# esp32_cam_rev_B.net
KiCad netlist of a schematic drawn in EAGLE
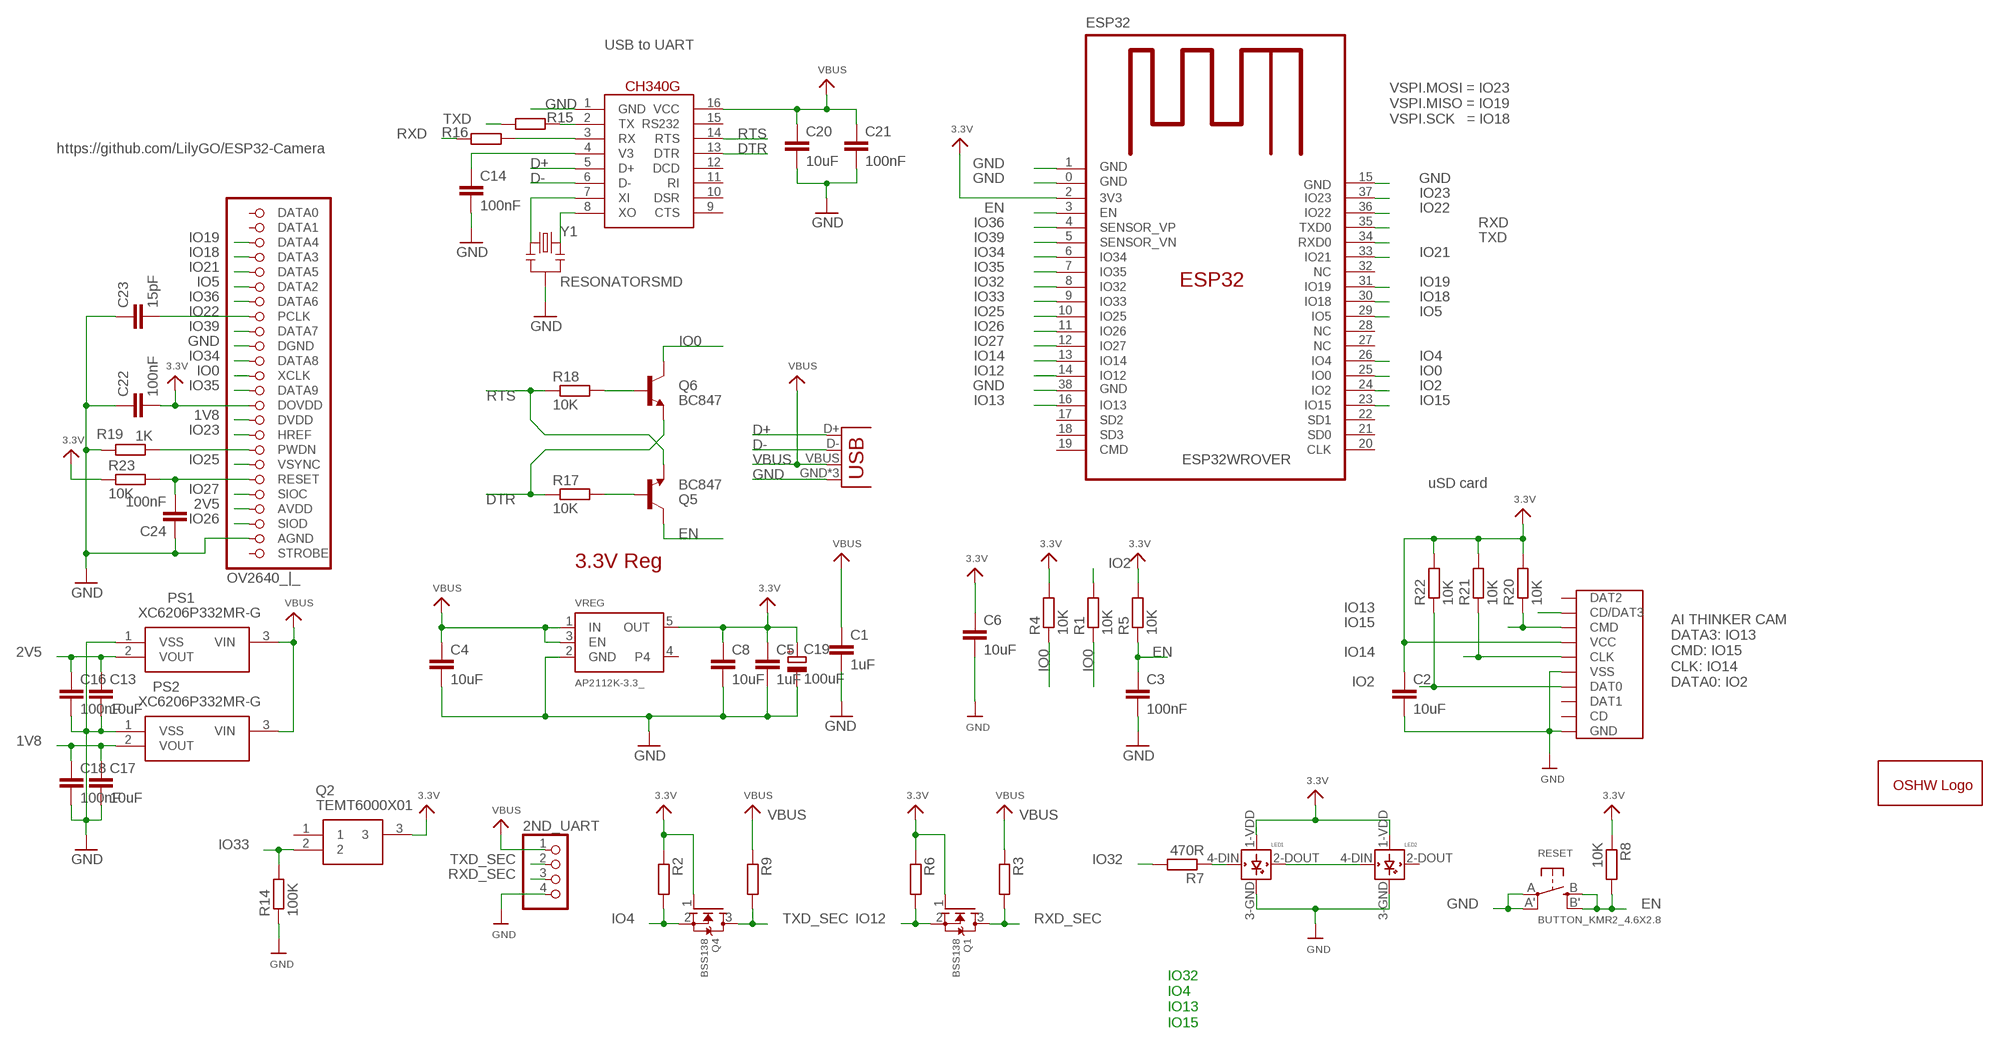
[diagram p0: schematic, sheet 1]

(export (version "E")
  (design (tool "Eeschema 10.0.6"))
  (components
    (comp (ref "2ND_UART")
      (value "JST_PH4")
      (footprint "eagle-import:JSTPH4")
      (libsource (lib "eagle-import") (part "JST_PH4"))
    )
    (comp (ref "C1")
      (value "1uF")
      (footprint "eagle-import:C0805K")
      (libsource (lib "eagle-import") (part "C-EUC0805K"))
    )
    (comp (ref "C2")
      (value "10uF")
      (footprint "eagle-import:C0805")
      (libsource (lib "eagle-import") (part "C-EUC0805"))
    )
    (comp (ref "C3")
      (value "100nF")
      (footprint "eagle-import:C0805K")
      (libsource (lib "eagle-import") (part "C-EUC0805K"))
    )
    (comp (ref "C4")
      (value "10uF")
      (footprint "eagle-import:C0805")
      (libsource (lib "eagle-import") (part "C-EUC0805"))
    )
    (comp (ref "C5")
      (value "1uF")
      (footprint "eagle-import:C0805")
      (libsource (lib "eagle-import") (part "C-EUC0805"))
    )
    (comp (ref "C6")
      (value "10uF")
      (footprint "eagle-import:C0805K")
      (libsource (lib "eagle-import") (part "C-EUC0805K"))
    )
    (comp (ref "C8")
      (value "10uF")
      (footprint "eagle-import:C0805")
      (libsource (lib "eagle-import") (part "C-EUC0805"))
    )
    (comp (ref "C13")
      (value "10uF")
      (footprint "eagle-import:C0805")
      (libsource (lib "eagle-import") (part "C-EUC0805"))
    )
    (comp (ref "C14")
      (value "100nF")
      (footprint "eagle-import:C0805K")
      (libsource (lib "eagle-import") (part "C-EUC0805K"))
    )
    (comp (ref "C16")
      (value "100nF")
      (footprint "eagle-import:C0805")
      (libsource (lib "eagle-import") (part "C-EUC0805"))
    )
    (comp (ref "C17")
      (value "10uF")
      (footprint "eagle-import:C0805")
      (libsource (lib "eagle-import") (part "C-EUC0805"))
    )
    (comp (ref "C18")
      (value "100nF")
      (footprint "eagle-import:C0805")
      (libsource (lib "eagle-import") (part "C-EUC0805"))
    )
    (comp (ref "C19")
      (value "100uF")
      (footprint "eagle-import:CT6032")
      (libsource (lib "eagle-import") (part "CPOL-EUCT6032"))
    )
    (comp (ref "C20")
      (value "10uF")
      (footprint "eagle-import:C0805")
      (libsource (lib "eagle-import") (part "C-EUC0805"))
    )
    (comp (ref "C21")
      (value "100nF")
      (footprint "eagle-import:C0805")
      (libsource (lib "eagle-import") (part "C-EUC0805"))
    )
    (comp (ref "C22")
      (value "100nF")
      (footprint "eagle-import:C0805")
      (libsource (lib "eagle-import") (part "C-EUC0805"))
    )
    (comp (ref "C23")
      (value "15pF")
      (footprint "eagle-import:C0805")
      (libsource (lib "eagle-import") (part "C-EUC0805"))
    )
    (comp (ref "C24")
      (value "100nF")
      (footprint "eagle-import:C0805")
      (libsource (lib "eagle-import") (part "C-EUC0805"))
    )
    (comp (ref "CH340G")
      (value "CH340G")
      (footprint "eagle-import:SO16")
      (libsource (lib "eagle-import") (part "CH340G"))
    )
    (comp (ref "ESP32")
      (value "ESP32WROVER")
      (footprint "eagle-import:ESP32WROVER")
      (libsource (lib "eagle-import") (part "ESP32WROVER"))
    )
    (comp (ref "FPC_CONNECTOR")
      (value "OV2640_|_")
      (footprint "eagle-import:5051102491")
      (libsource (lib "eagle-import") (part "OV2640_|_"))
    )
    (comp (ref "GOLD_ORB_SM1")
      (value "OSHWLOGO_")
      (footprint "eagle-import:OSHW_5MM_LOGO")
      (libsource (lib "eagle-import") (part "OSHWLOGO_"))
    )
    (comp (ref "LED1")
      (value "WS2812B")
      (footprint "eagle-import:WS2812B_5050")
      (libsource (lib "eagle-import") (part "WS2812B"))
    )
    (comp (ref "LED2")
      (value "WS2812B")
      (footprint "eagle-import:WS2812B_5050")
      (libsource (lib "eagle-import") (part "WS2812B"))
    )
    (comp (ref "PS1")
      (value "XC6206P332MR-G")
      (footprint "eagle-import:SOT95P280X130-3N")
      (fields (field (name "MOUSER_PART_NUMBER") "865-XC6206P332MR-G"))
      (libsource (lib "eagle-import") (part "XC6206P332MR-G"))
    )
    (comp (ref "PS2")
      (value "XC6206P332MR-G")
      (footprint "eagle-import:SOT95P280X130-3N")
      (fields (field (name "MOUSER_PART_NUMBER") "865-XC6206P332MR-G"))
      (libsource (lib "eagle-import") (part "XC6206P332MR-G"))
    )
    (comp (ref "Q1")
      (value "BSS138")
      (footprint "eagle-import:SOT95P240X110-3")
      (libsource (lib "eagle-import") (part "MOSFET_N_"))
    )
    (comp (ref "Q2")
      (value "TEMT6000X01")
      (footprint "eagle-import:TEMT6000X01")
      (fields (field (name "MOUSER_PART_NUMBER") "78-TEMT6000"))
      (libsource (lib "eagle-import") (part "TEMT6000X01"))
    )
    (comp (ref "Q4")
      (value "BSS138")
      (footprint "eagle-import:SOT95P240X110-3")
      (libsource (lib "eagle-import") (part "MOSFET_N_"))
    )
    (comp (ref "Q5")
      (value "BC847")
      (footprint "eagle-import:SOT23-3")
      (libsource (lib "eagle-import") (part "TRANSISTOR_NPNSOT23-3"))
    )
    (comp (ref "Q6")
      (value "BC847")
      (footprint "eagle-import:SOT23-3")
      (libsource (lib "eagle-import") (part "TRANSISTOR_NPNSOT23-3"))
    )
    (comp (ref "R1")
      (value "10K")
      (footprint "eagle-import:R0805")
      (libsource (lib "eagle-import") (part "R-EU_R0805"))
    )
    (comp (ref "R2")
      (value "10K")
      (footprint "eagle-import:R0805")
      (libsource (lib "eagle-import") (part "R-EU_R0805"))
    )
    (comp (ref "R3")
      (value "10K")
      (footprint "eagle-import:R0805")
      (libsource (lib "eagle-import") (part "R-EU_R0805"))
    )
    (comp (ref "R4")
      (value "10K")
      (footprint "eagle-import:R0805")
      (libsource (lib "eagle-import") (part "R-EU_R0805"))
    )
    (comp (ref "R5")
      (value "10K")
      (footprint "eagle-import:R0805")
      (libsource (lib "eagle-import") (part "R-EU_R0805"))
    )
    (comp (ref "R6")
      (value "10K")
      (footprint "eagle-import:R0805")
      (libsource (lib "eagle-import") (part "R-EU_R0805"))
    )
    (comp (ref "R7")
      (value "470R")
      (footprint "eagle-import:R0805")
      (libsource (lib "eagle-import") (part "R-EU_R0805"))
    )
    (comp (ref "R8")
      (value "10K")
      (footprint "eagle-import:R0805")
      (libsource (lib "eagle-import") (part "R-EU_R0805"))
    )
    (comp (ref "R9")
      (value "10K")
      (footprint "eagle-import:R0805")
      (libsource (lib "eagle-import") (part "R-EU_R0805"))
    )
    (comp (ref "R14")
      (value "100K")
      (footprint "eagle-import:R0805")
      (libsource (lib "eagle-import") (part "R-EU_R0805"))
    )
    (comp (ref "R15")
      (value "470R")
      (footprint "eagle-import:R0805")
      (libsource (lib "eagle-import") (part "R-EU_R0805"))
    )
    (comp (ref "R16")
      (value "470R")
      (footprint "eagle-import:R0805")
      (libsource (lib "eagle-import") (part "R-EU_R0805"))
    )
    (comp (ref "R17")
      (value "10K")
      (footprint "eagle-import:R0805")
      (libsource (lib "eagle-import") (part "R-EU_R0805"))
    )
    (comp (ref "R18")
      (value "10K")
      (footprint "eagle-import:R0805")
      (libsource (lib "eagle-import") (part "R-EU_R0805"))
    )
    (comp (ref "R19")
      (value "1K")
      (footprint "eagle-import:R0805")
      (libsource (lib "eagle-import") (part "R-EU_R0805"))
    )
    (comp (ref "R20")
      (value "10K")
      (footprint "eagle-import:R0805")
      (libsource (lib "eagle-import") (part "R-EU_R0805"))
    )
    (comp (ref "R21")
      (value "10K")
      (footprint "eagle-import:R0805")
      (libsource (lib "eagle-import") (part "R-EU_R0805"))
    )
    (comp (ref "R22")
      (value "10K")
      (footprint "eagle-import:R0805")
      (libsource (lib "eagle-import") (part "R-EU_R0805"))
    )
    (comp (ref "R23")
      (value "10K")
      (footprint "eagle-import:R0805")
      (libsource (lib "eagle-import") (part "R-EU_R0805"))
    )
    (comp (ref "RESET")
      (value "BUTTON_KMR2_4.6X2.8")
      (footprint "eagle-import:BUTTON_KMR2_4.6X2.8")
      (libsource (lib "eagle-import") (part "BUTTON_KMR2_4.6X2.8"))
    )
    (comp (ref "SD_CARD")
      (value "MICRO_SD_CARD_")
      (footprint "eagle-import:TFP09-2--12B")
      (libsource (lib "eagle-import") (part "MICRO_SD_CARD_"))
    )
    (comp (ref "USB")
      (value "USB_MICRO_ATTEND_")
      (footprint "eagle-import:USB_MICRO")
      (libsource (lib "eagle-import") (part "USB_MICRO_ATTEND_"))
    )
    (comp (ref "VREG")
      (value "AP2112K-3.3_")
      (footprint "eagle-import:SOT95P290X120-5")
      (libsource (lib "eagle-import") (part "AP2112K-3.3_"))
    )
    (comp (ref "Y1")
      (value "RESONATORSMD")
      (footprint "eagle-import:RESONATOR-SMD")
      (libsource (lib "eagle-import") (part "RESONATORSMD"))
    )
  )
  (nets
    (net (code "1") (name "/1V8") (class "Default")
      (node (ref "C17") (pin "1") (pinfunction "1_1") (pintype "passive"))
      (node (ref "C18") (pin "1") (pinfunction "1_1") (pintype "passive"))
      (node (ref "FPC_CONNECTOR") (pin "15") (pinfunction "DVDD_15") (pintype "passive"))
      (node (ref "PS2") (pin "2") (pinfunction "VOUT_2") (pintype "power_in"))
    )
    (net (code "2") (name "/2V5") (class "Default")
      (node (ref "C13") (pin "1") (pinfunction "1_1") (pintype "passive"))
      (node (ref "C16") (pin "1") (pinfunction "1_1") (pintype "passive"))
      (node (ref "FPC_CONNECTOR") (pin "21") (pinfunction "AVDD_21") (pintype "passive"))
      (node (ref "PS1") (pin "2") (pinfunction "VOUT_2") (pintype "power_in"))
    )
    (net (code "3") (name "/D+") (class "Default")
      (node (ref "CH340G") (pin "5") (pinfunction "D+_5") (pintype "bidirectional"))
      (node (ref "USB") (pin "D+") (pinfunction "D+_D+") (pintype "bidirectional"))
    )
    (net (code "4") (name "/D-") (class "Default")
      (node (ref "CH340G") (pin "6") (pinfunction "D-_6") (pintype "bidirectional"))
      (node (ref "USB") (pin "D-") (pinfunction "D-_D-") (pintype "bidirectional"))
    )
    (net (code "5") (name "/DTR") (class "Default")
      (node (ref "CH340G") (pin "13") (pinfunction "DTR_13") (pintype "bidirectional"))
      (node (ref "Q6") (pin "2") (pinfunction "E_2") (pintype "passive"))
      (node (ref "R17") (pin "1") (pinfunction "1_1") (pintype "passive"))
    )
    (net (code "6") (name "/EN") (class "Default")
      (node (ref "C3") (pin "1") (pinfunction "1_1") (pintype "passive"))
      (node (ref "ESP32") (pin "3") (pinfunction "EN_3") (pintype "bidirectional"))
      (node (ref "Q5") (pin "3") (pinfunction "C_3") (pintype "passive"))
      (node (ref "R5") (pin "1") (pinfunction "1_1") (pintype "passive"))
      (node (ref "R8") (pin "2") (pinfunction "2_2") (pintype "passive"))
      (node (ref "RESET") (pin "B") (pinfunction "S_B") (pintype "passive"))
      (node (ref "RESET") (pin "B'") (pinfunction "S1_B'") (pintype "passive"))
    )
    (net (code "7") (name "/IO0") (class "Default")
      (node (ref "ESP32") (pin "25") (pinfunction "IO0_25") (pintype "bidirectional"))
      (node (ref "FPC_CONNECTOR") (pin "12") (pinfunction "XCLK_12") (pintype "passive"))
      (node (ref "Q6") (pin "3") (pinfunction "C_3") (pintype "passive"))
      (node (ref "R1") (pin "1") (pinfunction "1_1") (pintype "passive"))
      (node (ref "R4") (pin "1") (pinfunction "1_1") (pintype "passive"))
    )
    (net (code "8") (name "/IO2") (class "Default")
      (node (ref "ESP32") (pin "24") (pinfunction "IO2_24") (pintype "bidirectional"))
      (node (ref "R1") (pin "2") (pinfunction "2_2") (pintype "passive"))
      (node (ref "R22") (pin "1") (pinfunction "1_1") (pintype "passive"))
      (node (ref "SD_CARD") (pin "DAT0") (pinfunction "DAT0_DAT0") (pintype "bidirectional"))
    )
    (net (code "9") (name "/IO4") (class "Default")
      (node (ref "ESP32") (pin "26") (pinfunction "IO4_26") (pintype "bidirectional"))
      (node (ref "Q4") (pin "2") (pinfunction "S_2") (pintype "bidirectional"))
      (node (ref "R2") (pin "2") (pinfunction "2_2") (pintype "passive"))
    )
    (net (code "10") (name "/IO5") (class "Default")
      (node (ref "ESP32") (pin "29") (pinfunction "IO5_29") (pintype "bidirectional"))
      (node (ref "FPC_CONNECTOR") (pin "6") (pinfunction "DATA2_6") (pintype "passive"))
    )
    (net (code "11") (name "/IO12") (class "Default")
      (node (ref "ESP32") (pin "14") (pinfunction "IO12_14") (pintype "bidirectional"))
      (node (ref "Q1") (pin "2") (pinfunction "S_2") (pintype "bidirectional"))
      (node (ref "R6") (pin "2") (pinfunction "2_2") (pintype "passive"))
    )
    (net (code "12") (name "/IO13") (class "Default")
      (node (ref "ESP32") (pin "16") (pinfunction "IO13_16") (pintype "bidirectional"))
      (node (ref "SD_CARD") (pin "CD/DAT3") (pinfunction "CD/DAT3_CD/DAT3") (pintype "bidirectional"))
    )
    (net (code "13") (name "/IO14") (class "Default")
      (node (ref "ESP32") (pin "13") (pinfunction "IO14_13") (pintype "bidirectional"))
      (node (ref "R21") (pin "1") (pinfunction "1_1") (pintype "passive"))
      (node (ref "SD_CARD") (pin "CLK") (pinfunction "CLK_CLK") (pintype "bidirectional"))
    )
    (net (code "14") (name "/IO15") (class "Default")
      (node (ref "ESP32") (pin "23") (pinfunction "IO15_23") (pintype "bidirectional"))
      (node (ref "R20") (pin "1") (pinfunction "1_1") (pintype "passive"))
      (node (ref "SD_CARD") (pin "CMD") (pinfunction "CMD_CMD") (pintype "bidirectional"))
    )
    (net (code "15") (name "/IO18") (class "Default")
      (node (ref "ESP32") (pin "30") (pinfunction "IO18_30") (pintype "bidirectional"))
      (node (ref "FPC_CONNECTOR") (pin "4") (pinfunction "DATA3_4") (pintype "passive"))
    )
    (net (code "16") (name "/IO19") (class "Default")
      (node (ref "ESP32") (pin "31") (pinfunction "IO19_31") (pintype "bidirectional"))
      (node (ref "FPC_CONNECTOR") (pin "3") (pinfunction "DATA4_3") (pintype "passive"))
    )
    (net (code "17") (name "/IO21") (class "Default")
      (node (ref "ESP32") (pin "33") (pinfunction "IO21_33") (pintype "bidirectional"))
      (node (ref "FPC_CONNECTOR") (pin "5") (pinfunction "DATA5_5") (pintype "passive"))
    )
    (net (code "18") (name "/IO22") (class "Default")
      (node (ref "C23") (pin "2") (pinfunction "2_2") (pintype "passive"))
      (node (ref "ESP32") (pin "36") (pinfunction "IO22_36") (pintype "bidirectional"))
      (node (ref "FPC_CONNECTOR") (pin "8") (pinfunction "PCLK_8") (pintype "passive"))
    )
    (net (code "19") (name "/IO23") (class "Default")
      (node (ref "ESP32") (pin "37") (pinfunction "IO23_37") (pintype "bidirectional"))
      (node (ref "FPC_CONNECTOR") (pin "16") (pinfunction "HREF_16") (pintype "passive"))
    )
    (net (code "20") (name "/IO25") (class "Default")
      (node (ref "ESP32") (pin "10") (pinfunction "IO25_10") (pintype "bidirectional"))
      (node (ref "FPC_CONNECTOR") (pin "18") (pinfunction "VSYNC_18") (pintype "passive"))
    )
    (net (code "21") (name "/IO26") (class "Default")
      (node (ref "ESP32") (pin "11") (pinfunction "IO26_11") (pintype "bidirectional"))
      (node (ref "FPC_CONNECTOR") (pin "22") (pinfunction "SIOD_22") (pintype "passive"))
    )
    (net (code "22") (name "/IO27") (class "Default")
      (node (ref "ESP32") (pin "12") (pinfunction "IO27_12") (pintype "bidirectional"))
      (node (ref "FPC_CONNECTOR") (pin "20") (pinfunction "SIOC_20") (pintype "passive"))
    )
    (net (code "23") (name "/IO32") (class "Default")
      (node (ref "ESP32") (pin "8") (pinfunction "IO32_8") (pintype "bidirectional"))
      (node (ref "R7") (pin "2") (pinfunction "2_2") (pintype "passive"))
    )
    (net (code "24") (name "/IO33") (class "Default")
      (node (ref "ESP32") (pin "9") (pinfunction "IO33_9") (pintype "bidirectional"))
      (node (ref "Q2") (pin "2") (pinfunction "2_2") (pintype "bidirectional"))
      (node (ref "R14") (pin "2") (pinfunction "2_2") (pintype "passive"))
    )
    (net (code "25") (name "/IO34") (class "Default")
      (node (ref "ESP32") (pin "6") (pinfunction "IO34_6") (pintype "bidirectional"))
      (node (ref "FPC_CONNECTOR") (pin "11") (pinfunction "DATA8_11") (pintype "passive"))
    )
    (net (code "26") (name "/IO35") (class "Default")
      (node (ref "ESP32") (pin "7") (pinfunction "IO35_7") (pintype "bidirectional"))
      (node (ref "FPC_CONNECTOR") (pin "13") (pinfunction "DATA9_13") (pintype "passive"))
    )
    (net (code "27") (name "/IO36") (class "Default")
      (node (ref "ESP32") (pin "4") (pinfunction "SENSOR_VP_4") (pintype "bidirectional"))
      (node (ref "FPC_CONNECTOR") (pin "7") (pinfunction "DATA6_7") (pintype "passive"))
    )
    (net (code "28") (name "/IO39") (class "Default")
      (node (ref "ESP32") (pin "5") (pinfunction "SENSOR_VN_5") (pintype "bidirectional"))
      (node (ref "FPC_CONNECTOR") (pin "9") (pinfunction "DATA7_9") (pintype "passive"))
    )
    (net (code "29") (name "/RTS") (class "Default")
      (node (ref "CH340G") (pin "14") (pinfunction "RTS_14") (pintype "bidirectional"))
      (node (ref "Q5") (pin "2") (pinfunction "E_2") (pintype "passive"))
      (node (ref "R18") (pin "1") (pinfunction "1_1") (pintype "passive"))
    )
    (net (code "30") (name "/RXD") (class "Default")
      (node (ref "ESP32") (pin "35") (pinfunction "TXD0_35") (pintype "bidirectional"))
      (node (ref "R16") (pin "2") (pinfunction "2_2") (pintype "passive"))
    )
    (net (code "31") (name "/RXD_SEC") (class "Default")
      (node (ref "2ND_UART") (pin "3") (pinfunction "3_3") (pintype "passive"))
      (node (ref "Q1") (pin "3") (pinfunction "D_3") (pintype "bidirectional"))
      (node (ref "R3") (pin "2") (pinfunction "2_2") (pintype "passive"))
    )
    (net (code "32") (name "/TXD") (class "Default")
      (node (ref "ESP32") (pin "34") (pinfunction "RXD0_34") (pintype "bidirectional"))
      (node (ref "R15") (pin "2") (pinfunction "2_2") (pintype "passive"))
    )
    (net (code "33") (name "/TXD_SEC") (class "Default")
      (node (ref "2ND_UART") (pin "2") (pinfunction "2_2") (pintype "passive"))
      (node (ref "Q4") (pin "3") (pinfunction "D_3") (pintype "bidirectional"))
      (node (ref "R9") (pin "2") (pinfunction "2_2") (pintype "passive"))
    )
    (net (code "34") (name "3.3V") (class "Default")
      (node (ref "C19") (pin "+") (pinfunction "+_+") (pintype "passive"))
      (node (ref "C2") (pin "1") (pinfunction "1_1") (pintype "passive"))
      (node (ref "C22") (pin "2") (pinfunction "2_2") (pintype "passive"))
      (node (ref "C5") (pin "1") (pinfunction "1_1") (pintype "passive"))
      (node (ref "C6") (pin "1") (pinfunction "1_1") (pintype "passive"))
      (node (ref "C8") (pin "1") (pinfunction "1_1") (pintype "passive"))
      (node (ref "ESP32") (pin "2") (pinfunction "3V3_2") (pintype "power_in"))
      (node (ref "FPC_CONNECTOR") (pin "14") (pinfunction "DOVDD_14") (pintype "passive"))
      (node (ref "LED1") (pin "1-VDD") (pinfunction "VDD_1-VDD") (pintype "power_in"))
      (node (ref "LED2") (pin "1-VDD") (pinfunction "VDD_1-VDD") (pintype "power_in"))
      (node (ref "Q1") (pin "1") (pinfunction "G_1") (pintype "bidirectional"))
      (node (ref "Q2") (pin "3") (pinfunction "3_3") (pintype "bidirectional"))
      (node (ref "Q4") (pin "1") (pinfunction "G_1") (pintype "bidirectional"))
      (node (ref "R2") (pin "1") (pinfunction "1_1") (pintype "passive"))
      (node (ref "R20") (pin "2") (pinfunction "2_2") (pintype "passive"))
      (node (ref "R21") (pin "2") (pinfunction "2_2") (pintype "passive"))
      (node (ref "R22") (pin "2") (pinfunction "2_2") (pintype "passive"))
      (node (ref "R23") (pin "1") (pinfunction "1_1") (pintype "passive"))
      (node (ref "R4") (pin "2") (pinfunction "2_2") (pintype "passive"))
      (node (ref "R5") (pin "2") (pinfunction "2_2") (pintype "passive"))
      (node (ref "R6") (pin "1") (pinfunction "1_1") (pintype "passive"))
      (node (ref "R8") (pin "1") (pinfunction "1_1") (pintype "passive"))
      (node (ref "SD_CARD") (pin "VCC") (pinfunction "VCC_VCC") (pintype "bidirectional"))
      (node (ref "VREG") (pin "5") (pinfunction "OUT_5") (pintype "bidirectional"))
    )
    (net (code "35") (name "GND") (class "Default")
      (node (ref "2ND_UART") (pin "4") (pinfunction "4_4") (pintype "passive"))
      (node (ref "C1") (pin "2") (pinfunction "2_2") (pintype "passive"))
      (node (ref "C13") (pin "2") (pinfunction "2_2") (pintype "passive"))
      (node (ref "C14") (pin "2") (pinfunction "2_2") (pintype "passive"))
      (node (ref "C16") (pin "2") (pinfunction "2_2") (pintype "passive"))
      (node (ref "C17") (pin "2") (pinfunction "2_2") (pintype "passive"))
      (node (ref "C18") (pin "2") (pinfunction "2_2") (pintype "passive"))
      (node (ref "C19") (pin "-") (pinfunction "-_-") (pintype "passive"))
      (node (ref "C2") (pin "2") (pinfunction "2_2") (pintype "passive"))
      (node (ref "C20") (pin "2") (pinfunction "2_2") (pintype "passive"))
      (node (ref "C21") (pin "2") (pinfunction "2_2") (pintype "passive"))
      (node (ref "C22") (pin "1") (pinfunction "1_1") (pintype "passive"))
      (node (ref "C23") (pin "1") (pinfunction "1_1") (pintype "passive"))
      (node (ref "C24") (pin "1") (pinfunction "1_1") (pintype "passive"))
      (node (ref "C3") (pin "2") (pinfunction "2_2") (pintype "passive"))
      (node (ref "C4") (pin "2") (pinfunction "2_2") (pintype "passive"))
      (node (ref "C5") (pin "2") (pinfunction "2_2") (pintype "passive"))
      (node (ref "C6") (pin "2") (pinfunction "2_2") (pintype "passive"))
      (node (ref "C8") (pin "2") (pinfunction "2_2") (pintype "passive"))
      (node (ref "CH340G") (pin "1") (pinfunction "GND_1") (pintype "bidirectional"))
      (node (ref "ESP32") (pin "0") (pinfunction "GND_0") (pintype "power_in"))
      (node (ref "ESP32") (pin "1") (pinfunction "GND_1") (pintype "power_in"))
      (node (ref "ESP32") (pin "15") (pinfunction "GND_15") (pintype "power_in"))
      (node (ref "ESP32") (pin "38") (pinfunction "GND_38") (pintype "power_in"))
      (node (ref "FPC_CONNECTOR") (pin "10") (pinfunction "DGND_10") (pintype "passive"))
      (node (ref "FPC_CONNECTOR") (pin "23") (pinfunction "AGND_23") (pintype "passive"))
      (node (ref "LED1") (pin "3-GND") (pinfunction "GND_3-GND") (pintype "power_in"))
      (node (ref "LED2") (pin "3-GND") (pinfunction "GND_3-GND") (pintype "power_in"))
      (node (ref "PS1") (pin "1") (pinfunction "VSS_1") (pintype "power_in"))
      (node (ref "PS2") (pin "1") (pinfunction "VSS_1") (pintype "power_in"))
      (node (ref "R14") (pin "1") (pinfunction "1_1") (pintype "passive"))
      (node (ref "R19") (pin "2") (pinfunction "2_2") (pintype "passive"))
      (node (ref "RESET") (pin "A") (pinfunction "P_A") (pintype "passive"))
      (node (ref "RESET") (pin "A'") (pinfunction "P1_A'") (pintype "passive"))
      (node (ref "SD_CARD") (pin "GND") (pinfunction "GND_GND") (pintype "bidirectional"))
      (node (ref "SD_CARD") (pin "GND@1") (pinfunction "GND_GND@1") (pintype "bidirectional"))
      (node (ref "SD_CARD") (pin "GND@2") (pinfunction "GND_GND@2") (pintype "bidirectional"))
      (node (ref "SD_CARD") (pin "GND@3") (pinfunction "VSS_GND@3") (pintype "bidirectional"))
      (node (ref "SD_CARD") (pin "VSS") (pinfunction "GND_VSS") (pintype "bidirectional"))
      (node (ref "USB") (pin "GND") (pinfunction "GND_GND") (pintype "bidirectional"))
      (node (ref "USB") (pin "GND@2") (pinfunction "GND_GND@2") (pintype "bidirectional"))
      (node (ref "USB") (pin "GND@3") (pinfunction "GND_GND@3") (pintype "bidirectional"))
      (node (ref "VREG") (pin "2") (pinfunction "GND_2") (pintype "bidirectional"))
      (node (ref "Y1") (pin "2") (pinfunction "2_2") (pintype "passive"))
    )
    (net (code "36") (name "Net-(CH340G-RX)") (class "Default")
      (node (ref "CH340G") (pin "3") (pinfunction "RX_3") (pintype "bidirectional"))
      (node (ref "R16") (pin "1") (pinfunction "1_1") (pintype "passive"))
    )
    (net (code "37") (name "Net-(CH340G-TX)") (class "Default")
      (node (ref "CH340G") (pin "2") (pinfunction "TX_2") (pintype "bidirectional"))
      (node (ref "R15") (pin "1") (pinfunction "1_1") (pintype "passive"))
    )
    (net (code "38") (name "Net-(CH340G-V3)") (class "Default")
      (node (ref "C14") (pin "1") (pinfunction "1_1") (pintype "passive"))
      (node (ref "CH340G") (pin "4") (pinfunction "V3_4") (pintype "bidirectional"))
    )
    (net (code "39") (name "Net-(CH340G-XI)") (class "Default")
      (node (ref "CH340G") (pin "7") (pinfunction "XI_7") (pintype "bidirectional"))
      (node (ref "Y1") (pin "1") (pinfunction "1_1") (pintype "passive"))
    )
    (net (code "40") (name "Net-(CH340G-XO)") (class "Default")
      (node (ref "CH340G") (pin "8") (pinfunction "XO_8") (pintype "bidirectional"))
      (node (ref "Y1") (pin "3") (pinfunction "3_3") (pintype "passive"))
    )
    (net (code "41") (name "Net-(FPC_CONNECTOR-PWDN)") (class "Default")
      (node (ref "FPC_CONNECTOR") (pin "17") (pinfunction "PWDN_17") (pintype "passive"))
      (node (ref "R19") (pin "1") (pinfunction "1_1") (pintype "passive"))
    )
    (net (code "42") (name "Net-(FPC_CONNECTOR-RESET)") (class "Default")
      (node (ref "C24") (pin "2") (pinfunction "2_2") (pintype "passive"))
      (node (ref "FPC_CONNECTOR") (pin "19") (pinfunction "RESET_19") (pintype "passive"))
      (node (ref "R23") (pin "2") (pinfunction "2_2") (pintype "passive"))
    )
    (net (code "43") (name "Net-(LED1-DIN)") (class "Default")
      (node (ref "LED1") (pin "4-DIN") (pinfunction "DIN_4-DIN") (pintype "input"))
      (node (ref "R7") (pin "1") (pinfunction "1_1") (pintype "passive"))
    )
    (net (code "44") (name "Net-(LED1-DOUT)") (class "Default")
      (node (ref "LED1") (pin "2-DOUT") (pinfunction "DOUT_2-DOUT") (pintype "output"))
      (node (ref "LED2") (pin "4-DIN") (pinfunction "DIN_4-DIN") (pintype "input"))
    )
    (net (code "45") (name "Net-(Q5-B)") (class "Default")
      (node (ref "Q5") (pin "1") (pinfunction "B_1") (pintype "passive"))
      (node (ref "R17") (pin "2") (pinfunction "2_2") (pintype "passive"))
    )
    (net (code "46") (name "Net-(Q6-B)") (class "Default")
      (node (ref "Q6") (pin "1") (pinfunction "B_1") (pintype "passive"))
      (node (ref "R18") (pin "2") (pinfunction "2_2") (pintype "passive"))
    )
    (net (code "47") (name "VBUS") (class "Default")
      (node (ref "2ND_UART") (pin "1") (pinfunction "1_1") (pintype "passive"))
      (node (ref "C1") (pin "1") (pinfunction "1_1") (pintype "passive"))
      (node (ref "C20") (pin "1") (pinfunction "1_1") (pintype "passive"))
      (node (ref "C21") (pin "1") (pinfunction "1_1") (pintype "passive"))
      (node (ref "C4") (pin "1") (pinfunction "1_1") (pintype "passive"))
      (node (ref "CH340G") (pin "16") (pinfunction "VCC_16") (pintype "bidirectional"))
      (node (ref "PS1") (pin "3") (pinfunction "VIN_3") (pintype "power_in"))
      (node (ref "PS2") (pin "3") (pinfunction "VIN_3") (pintype "power_in"))
      (node (ref "R3") (pin "1") (pinfunction "1_1") (pintype "passive"))
      (node (ref "R9") (pin "1") (pinfunction "1_1") (pintype "passive"))
      (node (ref "USB") (pin "VBUS") (pinfunction "VBUS_VBUS") (pintype "bidirectional"))
      (node (ref "VREG") (pin "1") (pinfunction "IN_1") (pintype "bidirectional"))
      (node (ref "VREG") (pin "3") (pinfunction "EN_3") (pintype "bidirectional"))
    )
    (net (code "48") (name "unconnected-(CH340G-CTS-Pad9)") (class "Default")
      (node (ref "CH340G") (pin "9") (pinfunction "CTS_9") (pintype "bidirectional"))
    )
    (net (code "49") (name "unconnected-(CH340G-DCD-Pad12)") (class "Default")
      (node (ref "CH340G") (pin "12") (pinfunction "DCD_12") (pintype "bidirectional"))
    )
    (net (code "50") (name "unconnected-(CH340G-DSR-Pad10)") (class "Default")
      (node (ref "CH340G") (pin "10") (pinfunction "DSR_10") (pintype "bidirectional"))
    )
    (net (code "51") (name "unconnected-(CH340G-RI-Pad11)") (class "Default")
      (node (ref "CH340G") (pin "11") (pinfunction "RI_11") (pintype "bidirectional"))
    )
    (net (code "52") (name "unconnected-(CH340G-RS232-Pad15)") (class "Default")
      (node (ref "CH340G") (pin "15") (pinfunction "RS232_15") (pintype "bidirectional"))
    )
    (net (code "53") (name "unconnected-(ESP32-CLK-Pad20)") (class "Default")
      (node (ref "ESP32") (pin "20") (pinfunction "CLK_20") (pintype "bidirectional"))
    )
    (net (code "54") (name "unconnected-(ESP32-CMD-Pad19)") (class "Default")
      (node (ref "ESP32") (pin "19") (pinfunction "CMD_19") (pintype "bidirectional"))
    )
    (net (code "55") (name "unconnected-(ESP32-NC-Pad27)") (class "Default")
      (node (ref "ESP32") (pin "27") (pinfunction "NC_27") (pintype "bidirectional"))
    )
    (net (code "56") (name "unconnected-(ESP32-NC-Pad28)") (class "Default")
      (node (ref "ESP32") (pin "28") (pinfunction "NC_28") (pintype "bidirectional"))
    )
    (net (code "57") (name "unconnected-(ESP32-NC-Pad32)") (class "Default")
      (node (ref "ESP32") (pin "32") (pinfunction "NC_32") (pintype "bidirectional"))
    )
    (net (code "58") (name "unconnected-(ESP32-SD0-Pad21)") (class "Default")
      (node (ref "ESP32") (pin "21") (pinfunction "SD0_21") (pintype "bidirectional"))
    )
    (net (code "59") (name "unconnected-(ESP32-SD1-Pad22)") (class "Default")
      (node (ref "ESP32") (pin "22") (pinfunction "SD1_22") (pintype "bidirectional"))
    )
    (net (code "60") (name "unconnected-(ESP32-SD2-Pad17)") (class "Default")
      (node (ref "ESP32") (pin "17") (pinfunction "SD2_17") (pintype "bidirectional"))
    )
    (net (code "61") (name "unconnected-(ESP32-SD3-Pad18)") (class "Default")
      (node (ref "ESP32") (pin "18") (pinfunction "SD3_18") (pintype "bidirectional"))
    )
    (net (code "62") (name "unconnected-(FPC_CONNECTOR-DATA0-Pad1)") (class "Default")
      (node (ref "FPC_CONNECTOR") (pin "1") (pinfunction "DATA0_1") (pintype "passive"))
    )
    (net (code "63") (name "unconnected-(FPC_CONNECTOR-DATA1-Pad2)") (class "Default")
      (node (ref "FPC_CONNECTOR") (pin "2") (pinfunction "DATA1_2") (pintype "passive"))
    )
    (net (code "64") (name "unconnected-(FPC_CONNECTOR-STROBE-Pad24)") (class "Default")
      (node (ref "FPC_CONNECTOR") (pin "24") (pinfunction "STROBE_24") (pintype "passive"))
    )
    (net (code "65") (name "unconnected-(LED2-DOUT-Pad2-DOUT)") (class "Default")
      (node (ref "LED2") (pin "2-DOUT") (pinfunction "DOUT_2-DOUT") (pintype "output"))
    )
    (net (code "66") (name "unconnected-(Q2-Pad1)") (class "Default")
      (node (ref "Q2") (pin "1") (pinfunction "1_1") (pintype "bidirectional"))
    )
    (net (code "67") (name "unconnected-(SD_CARD-PadCD)") (class "Default")
      (node (ref "SD_CARD") (pin "CD") (pinfunction "CD_CD") (pintype "bidirectional"))
    )
    (net (code "68") (name "unconnected-(SD_CARD-PadDAT1)") (class "Default")
      (node (ref "SD_CARD") (pin "DAT1") (pinfunction "DAT1_DAT1") (pintype "bidirectional"))
    )
    (net (code "69") (name "unconnected-(SD_CARD-PadDAT2)") (class "Default")
      (node (ref "SD_CARD") (pin "DAT2") (pinfunction "DAT2_DAT2") (pintype "bidirectional"))
    )
    (net (code "70") (name "unconnected-(VREG-P4-Pad4)") (class "Default")
      (node (ref "VREG") (pin "4") (pinfunction "P4_4") (pintype "bidirectional"))
    )
  )
)
